# 1.net
KiCad netlist of a schematic drawn in EasyEDA Pro
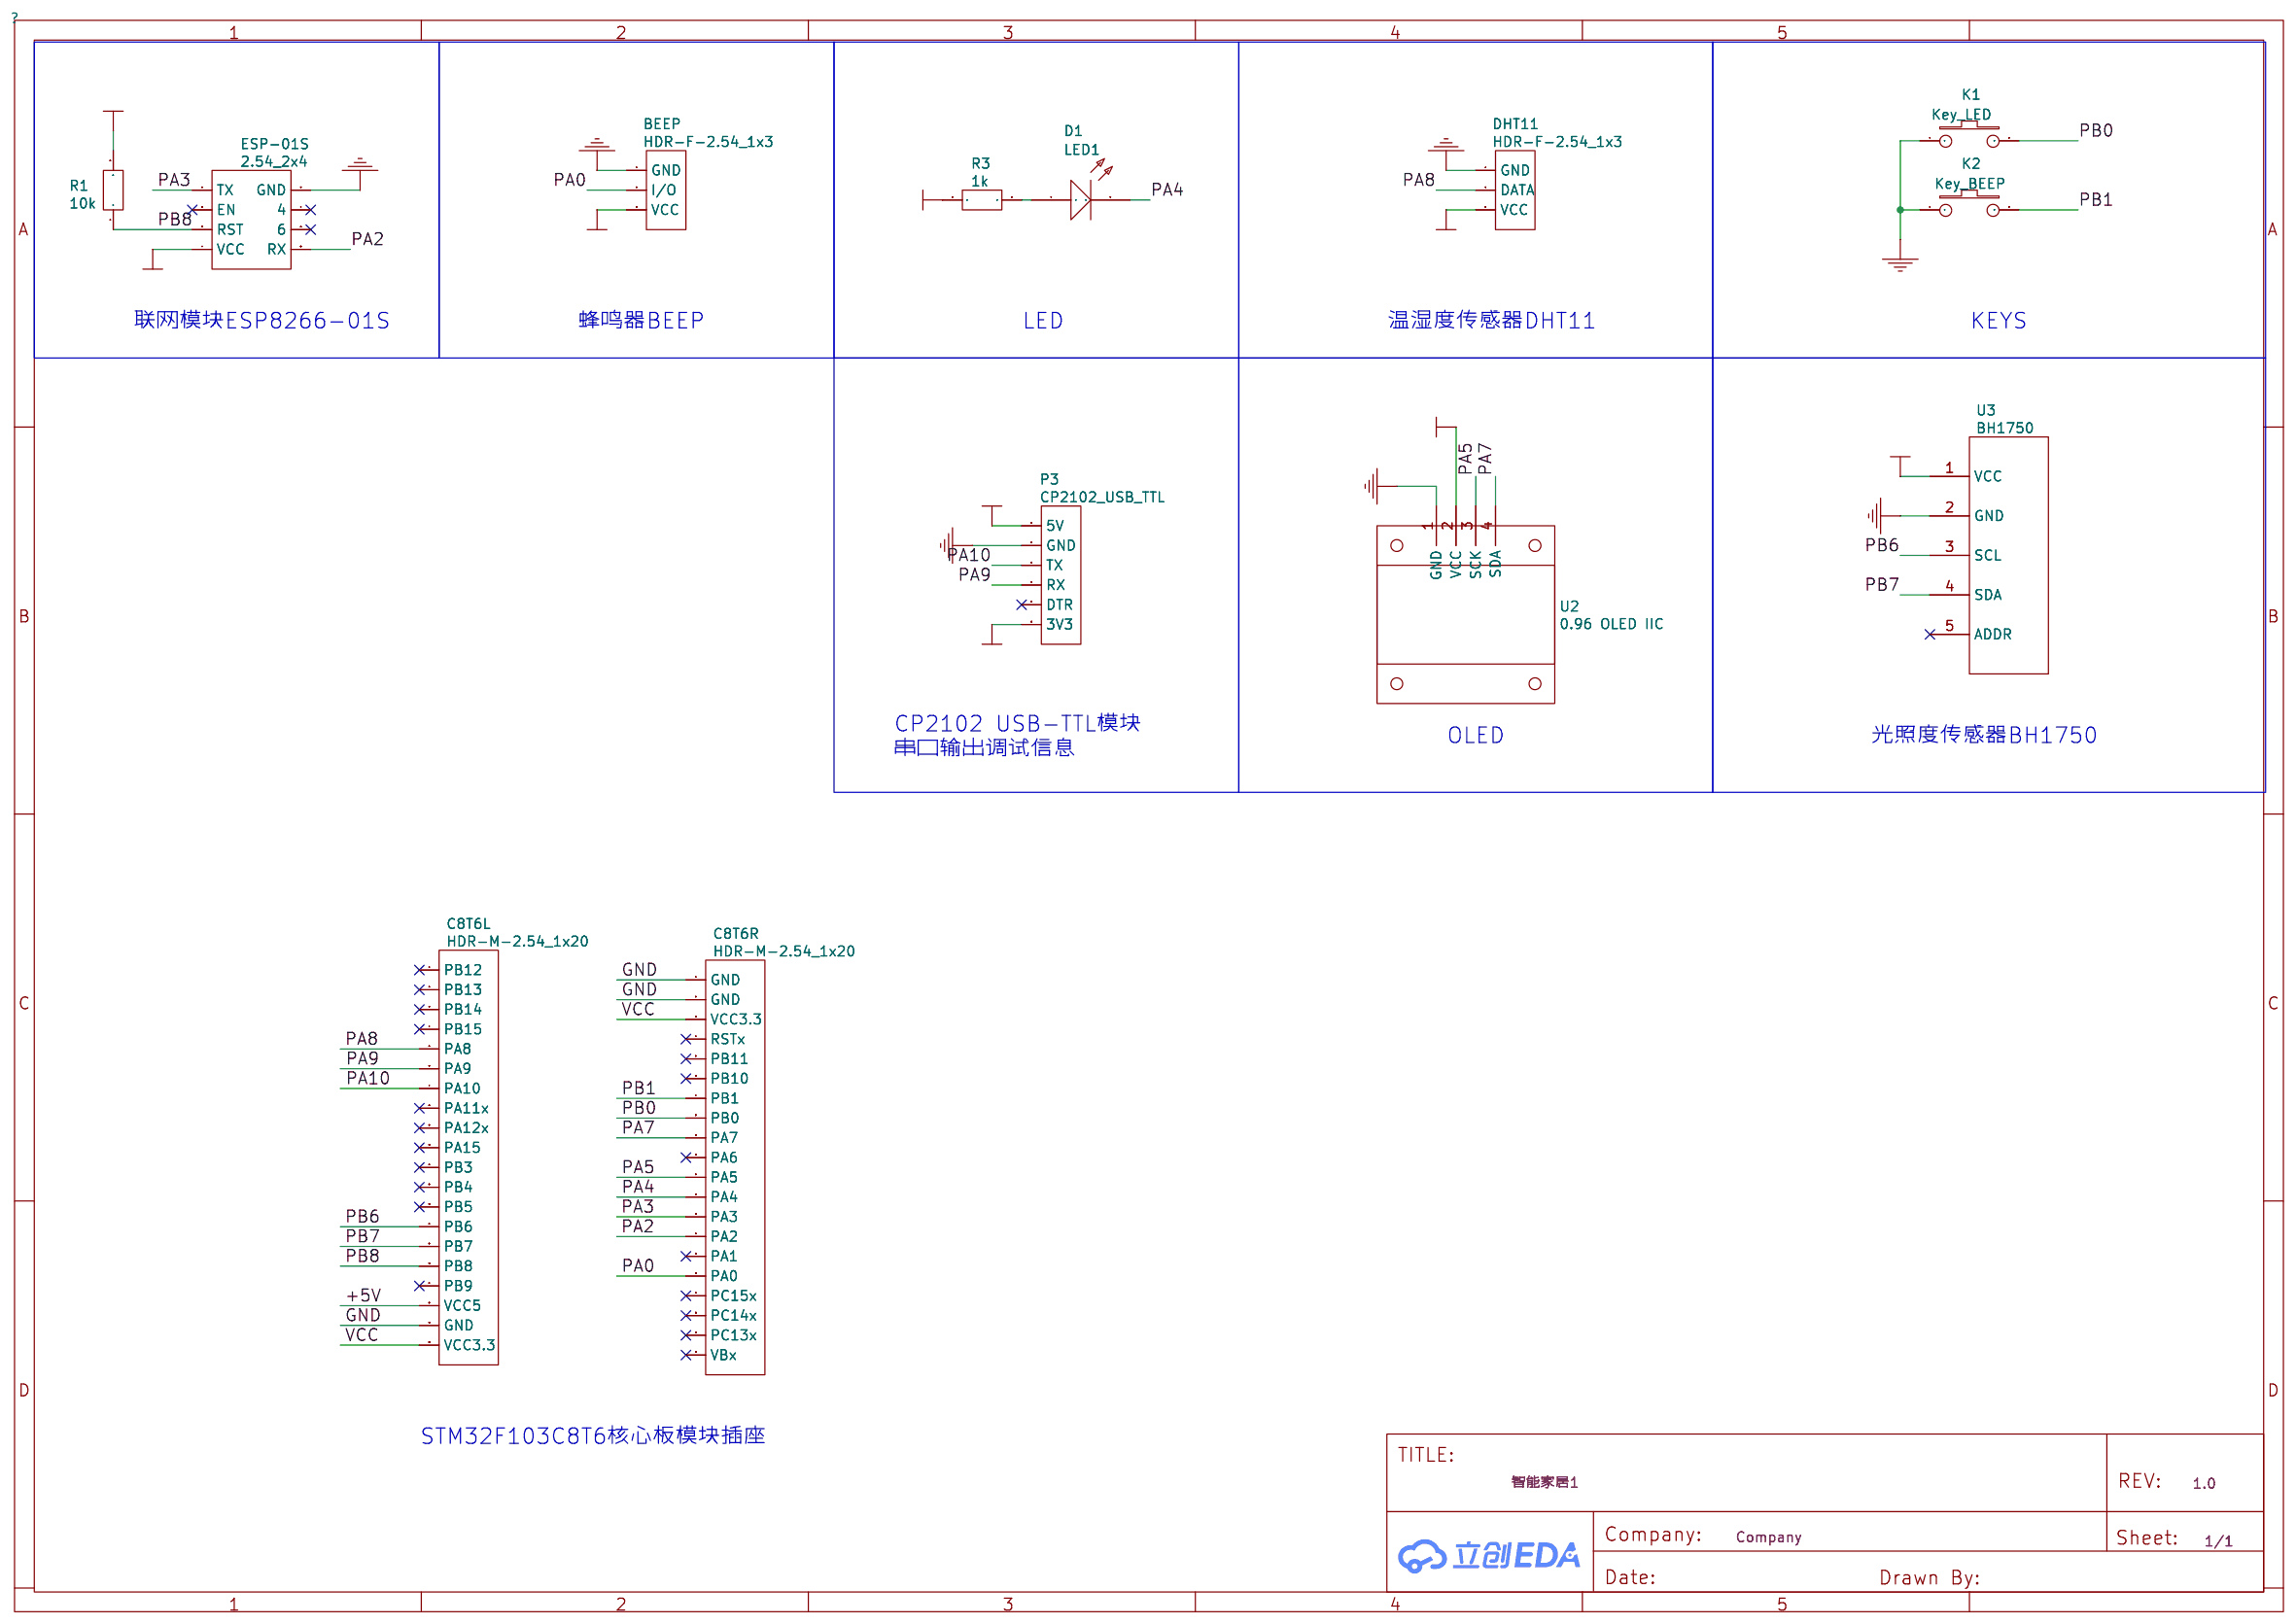
[diagram p0: schematic sheet]

(export (version "E")
  (design (tool "Eeschema 10.0.6"))
  (components
    (comp (ref "BEEP") (value "HDR-F-2.54_1x3") (libsource (lib "") (part "HDR-F-2.54_1x3_1")))
    (comp (ref "C8T6L")
      (value "HDR-M-2.54_1x20")
      (fields
        (field (name "Manufacturer Part") "2.54mm 1*20P Female header")
        (field (name "Manufacturer") "BOOMELE")
      )
      (libsource (lib "easyedapro") (part "HDR-M-2.54_1x20"))
    )
    (comp (ref "C8T6R")
      (value "HDR-M-2.54_1x20")
      (fields
        (field (name "Manufacturer Part") "2.54mm 1*20P Female header")
        (field (name "Manufacturer") "BOOMELE")
      )
      (libsource (lib "") (part "HDR-M-2.54_1x20_1"))
    )
    (comp (ref "D1") (value "LED1") (libsource (lib "easyedapro") (part "LED1")))
    (comp (ref "DHT11") (value "HDR-F-2.54_1x3") (libsource (lib "easyedapro") (part "HDR-F-2.54_1x3")))
    (comp (ref "ESP-01S") (value "2.54_2x4") (libsource (lib "easyedapro") (part "2.54_2x4")))
    (comp (ref "K1") (value "Key_LED") (libsource (lib "easyedapro") (part "Key_LED")))
    (comp (ref "K2") (value "Key_BEEP") (libsource (lib "easyedapro") (part "Key_BEEP")))
    (comp (ref "P3")
      (value "CP2102_USB_TTL")
      (fields (field (name "Manufacturer Part") "Female header 1*6p") (field (name "Manufacturer") "BOOMELE"))
      (libsource (lib "easyedapro") (part "CP2102_USB_TTL"))
    )
    (comp (ref "R1") (value "10k") (libsource (lib "easyedapro") (part "10k")))
    (comp (ref "R3") (value "1k") (libsource (lib "easyedapro") (part "1k")))
    (comp (ref "U2")
      (value "0.96 OLED IIC")
      (fields (field (name "Manufacturer Part") "0.96 OLED"))
      (libsource (lib "easyedapro") (part "0.96 OLED IIC"))
    )
    (comp (ref "U3") (value "BH1750") (libsource (lib "easyedapro") (part "BH1750")))
  )
  (nets
    (net (code "1") (name "+5V") (class "Default")
      (node (ref "C8T6L") (pin "18") (pinfunction "VCC5_18") (pintype "input"))
      (node (ref "P3") (pin "1") (pinfunction "5V_1") (pintype "input"))
    )
    (net (code "2") (name "/PA0") (class "Default")
      (node (ref "BEEP") (pin "2") (pinfunction "I/O_2") (pintype "input"))
      (node (ref "C8T6R") (pin "16") (pinfunction "PA0_16") (pintype "input"))
    )
    (net (code "3") (name "/PA2") (class "Default")
      (node (ref "C8T6R") (pin "14") (pinfunction "PA2_14") (pintype "input"))
      (node (ref "ESP-01S") (pin "8") (pinfunction "RX_8") (pintype "unspecified"))
    )
    (net (code "4") (name "/PA3") (class "Default")
      (node (ref "C8T6R") (pin "13") (pinfunction "PA3_13") (pintype "input"))
      (node (ref "ESP-01S") (pin "1") (pinfunction "TX_1") (pintype "unspecified"))
    )
    (net (code "5") (name "/PA4") (class "Default")
      (node (ref "C8T6R") (pin "12") (pinfunction "PA4_12") (pintype "input"))
      (node (ref "D1") (pin "2") (pinfunction "K_2") (pintype "unspecified"))
    )
    (net (code "6") (name "/PA5") (class "Default")
      (node (ref "C8T6R") (pin "11") (pinfunction "PA5_11") (pintype "input"))
      (node (ref "U2") (pin "3") (pinfunction "SCK_3") (pintype "unspecified"))
    )
    (net (code "7") (name "/PA7") (class "Default")
      (node (ref "C8T6R") (pin "9") (pinfunction "PA7_9") (pintype "input"))
      (node (ref "U2") (pin "4") (pinfunction "SDA_4") (pintype "unspecified"))
    )
    (net (code "8") (name "/PA8") (class "Default")
      (node (ref "C8T6L") (pin "5") (pinfunction "PA8_5") (pintype "input"))
      (node (ref "DHT11") (pin "2") (pinfunction "DATA_2") (pintype "input"))
    )
    (net (code "9") (name "/PA9") (class "Default")
      (node (ref "C8T6L") (pin "6") (pinfunction "PA9_6") (pintype "input"))
      (node (ref "P3") (pin "4") (pinfunction "RX_4") (pintype "input"))
    )
    (net (code "10") (name "/PA10") (class "Default")
      (node (ref "C8T6L") (pin "7") (pinfunction "PA10_7") (pintype "input"))
      (node (ref "P3") (pin "3") (pinfunction "TX_3") (pintype "input"))
    )
    (net (code "11") (name "/PB0") (class "Default")
      (node (ref "C8T6R") (pin "8") (pinfunction "PB0_8") (pintype "input"))
      (node (ref "K1") (pin "2") (pinfunction "2_2") (pintype "unspecified"))
    )
    (net (code "12") (name "/PB1") (class "Default")
      (node (ref "C8T6R") (pin "7") (pinfunction "PB1_7") (pintype "input"))
      (node (ref "K2") (pin "2") (pinfunction "2_2") (pintype "unspecified"))
    )
    (net (code "13") (name "/PB6") (class "Default")
      (node (ref "C8T6L") (pin "14") (pinfunction "PB6_14") (pintype "input"))
      (node (ref "U3") (pin "3") (pinfunction "SCL_3") (pintype "unspecified"))
    )
    (net (code "14") (name "/PB7") (class "Default")
      (node (ref "C8T6L") (pin "15") (pinfunction "PB7_15") (pintype "input"))
      (node (ref "U3") (pin "4") (pinfunction "SDA_4") (pintype "unspecified"))
    )
    (net (code "15") (name "/PB8") (class "Default")
      (node (ref "C8T6L") (pin "16") (pinfunction "PB8_16") (pintype "input"))
      (node (ref "ESP-01S") (pin "5") (pinfunction "RST_5") (pintype "unspecified"))
      (node (ref "R1") (pin "1") (pinfunction "1_1") (pintype "unspecified"))
    )
    (net (code "16") (name "GND") (class "Default")
      (node (ref "BEEP") (pin "1") (pinfunction "GND_1") (pintype "input"))
      (node (ref "C8T6L") (pin "19") (pinfunction "GND_19") (pintype "input"))
      (node (ref "C8T6R") (pin "1") (pinfunction "GND_1") (pintype "input"))
      (node (ref "C8T6R") (pin "2") (pinfunction "GND_2") (pintype "input"))
      (node (ref "DHT11") (pin "1") (pinfunction "GND_1") (pintype "input"))
      (node (ref "ESP-01S") (pin "2") (pinfunction "GND_2") (pintype "unspecified"))
      (node (ref "K1") (pin "1") (pinfunction "1_1") (pintype "unspecified"))
      (node (ref "K2") (pin "1") (pinfunction "1_1") (pintype "unspecified"))
      (node (ref "P3") (pin "2") (pinfunction "GND_2") (pintype "input"))
      (node (ref "U2") (pin "1") (pinfunction "GND_1") (pintype "unspecified"))
      (node (ref "U3") (pin "2") (pinfunction "GND_2") (pintype "unspecified"))
    )
    (net (code "17") (name "Net-(D1-A)") (class "Default")
      (node (ref "D1") (pin "1") (pinfunction "A_1") (pintype "unspecified"))
      (node (ref "R3") (pin "2") (pinfunction "2_2") (pintype "unspecified"))
    )
    (net (code "18") (name "VCC") (class "Default")
      (node (ref "BEEP") (pin "3") (pinfunction "VCC_3") (pintype "input"))
      (node (ref "C8T6L") (pin "20") (pinfunction "VCC3.3_20") (pintype "input"))
      (node (ref "C8T6R") (pin "3") (pinfunction "VCC3.3_3") (pintype "input"))
      (node (ref "DHT11") (pin "3") (pinfunction "VCC_3") (pintype "input"))
      (node (ref "ESP-01S") (pin "7") (pinfunction "VCC_7") (pintype "unspecified"))
      (node (ref "P3") (pin "6") (pinfunction "3V3_6") (pintype "input"))
      (node (ref "R1") (pin "2") (pinfunction "2_2") (pintype "unspecified"))
      (node (ref "R3") (pin "1") (pinfunction "1_1") (pintype "unspecified"))
      (node (ref "U2") (pin "2") (pinfunction "VCC_2") (pintype "unspecified"))
      (node (ref "U3") (pin "1") (pinfunction "VCC_1") (pintype "unspecified"))
    )
    (net (code "19") (name "unconnected-(C8T6L-PA11x-Pad8)") (class "Default")
      (node (ref "C8T6L") (pin "8") (pinfunction "PA11x_8") (pintype "input+no_connect"))
    )
    (net (code "20") (name "unconnected-(C8T6L-PA12x-Pad9)") (class "Default")
      (node (ref "C8T6L") (pin "9") (pinfunction "PA12x_9") (pintype "input+no_connect"))
    )
    (net (code "21") (name "unconnected-(C8T6L-PA15-Pad10)") (class "Default")
      (node (ref "C8T6L") (pin "10") (pinfunction "PA15_10") (pintype "input+no_connect"))
    )
    (net (code "22") (name "unconnected-(C8T6L-PB3-Pad11)") (class "Default")
      (node (ref "C8T6L") (pin "11") (pinfunction "PB3_11") (pintype "input+no_connect"))
    )
    (net (code "23") (name "unconnected-(C8T6L-PB4-Pad12)") (class "Default")
      (node (ref "C8T6L") (pin "12") (pinfunction "PB4_12") (pintype "input+no_connect"))
    )
    (net (code "24") (name "unconnected-(C8T6L-PB5-Pad13)") (class "Default")
      (node (ref "C8T6L") (pin "13") (pinfunction "PB5_13") (pintype "input+no_connect"))
    )
    (net (code "25") (name "unconnected-(C8T6L-PB9-Pad17)") (class "Default")
      (node (ref "C8T6L") (pin "17") (pinfunction "PB9_17") (pintype "input+no_connect"))
    )
    (net (code "26") (name "unconnected-(C8T6L-PB12-Pad1)") (class "Default")
      (node (ref "C8T6L") (pin "1") (pinfunction "PB12_1") (pintype "input+no_connect"))
    )
    (net (code "27") (name "unconnected-(C8T6L-PB13-Pad2)") (class "Default")
      (node (ref "C8T6L") (pin "2") (pinfunction "PB13_2") (pintype "input+no_connect"))
    )
    (net (code "28") (name "unconnected-(C8T6L-PB14-Pad3)") (class "Default")
      (node (ref "C8T6L") (pin "3") (pinfunction "PB14_3") (pintype "input+no_connect"))
    )
    (net (code "29") (name "unconnected-(C8T6L-PB15-Pad4)") (class "Default")
      (node (ref "C8T6L") (pin "4") (pinfunction "PB15_4") (pintype "input+no_connect"))
    )
    (net (code "30") (name "unconnected-(C8T6R-PA1-Pad15)") (class "Default")
      (node (ref "C8T6R") (pin "15") (pinfunction "PA1_15") (pintype "input+no_connect"))
    )
    (net (code "31") (name "unconnected-(C8T6R-PA6-Pad10)") (class "Default")
      (node (ref "C8T6R") (pin "10") (pinfunction "PA6_10") (pintype "input+no_connect"))
    )
    (net (code "32") (name "unconnected-(C8T6R-PB10-Pad6)") (class "Default")
      (node (ref "C8T6R") (pin "6") (pinfunction "PB10_6") (pintype "input+no_connect"))
    )
    (net (code "33") (name "unconnected-(C8T6R-PB11-Pad5)") (class "Default")
      (node (ref "C8T6R") (pin "5") (pinfunction "PB11_5") (pintype "input+no_connect"))
    )
    (net (code "34") (name "unconnected-(C8T6R-PC13x-Pad19)") (class "Default")
      (node (ref "C8T6R") (pin "19") (pinfunction "PC13x_19") (pintype "input+no_connect"))
    )
    (net (code "35") (name "unconnected-(C8T6R-PC14x-Pad18)") (class "Default")
      (node (ref "C8T6R") (pin "18") (pinfunction "PC14x_18") (pintype "input+no_connect"))
    )
    (net (code "36") (name "unconnected-(C8T6R-PC15x-Pad17)") (class "Default")
      (node (ref "C8T6R") (pin "17") (pinfunction "PC15x_17") (pintype "input+no_connect"))
    )
    (net (code "37") (name "unconnected-(C8T6R-RSTx-Pad4)") (class "Default")
      (node (ref "C8T6R") (pin "4") (pinfunction "RSTx_4") (pintype "input+no_connect"))
    )
    (net (code "38") (name "unconnected-(C8T6R-VBx-Pad20)") (class "Default")
      (node (ref "C8T6R") (pin "20") (pinfunction "VBx_20") (pintype "input+no_connect"))
    )
    (net (code "39") (name "unconnected-(ESP-01S-EN-Pad3)") (class "Default")
      (node (ref "ESP-01S") (pin "3") (pinfunction "EN_3") (pintype "unspecified+no_connect"))
    )
    (net (code "40") (name "unconnected-(ESP-01S-Pad4)") (class "Default")
      (node (ref "ESP-01S") (pin "4") (pinfunction "4_4") (pintype "unspecified+no_connect"))
    )
    (net (code "41") (name "unconnected-(ESP-01S-Pad6)") (class "Default")
      (node (ref "ESP-01S") (pin "6") (pinfunction "6_6") (pintype "unspecified+no_connect"))
    )
    (net (code "42") (name "unconnected-(P3-DTR-Pad5)") (class "Default")
      (node (ref "P3") (pin "5") (pinfunction "DTR_5") (pintype "input+no_connect"))
    )
    (net (code "43") (name "unconnected-(U3-ADDR-Pad5)") (class "Default")
      (node (ref "U3") (pin "5") (pinfunction "ADDR_5") (pintype "unspecified+no_connect"))
    )
  )
)
